# CopernicusBasicTestCircuit.net
KiCad netlist of a schematic drawn in EAGLE
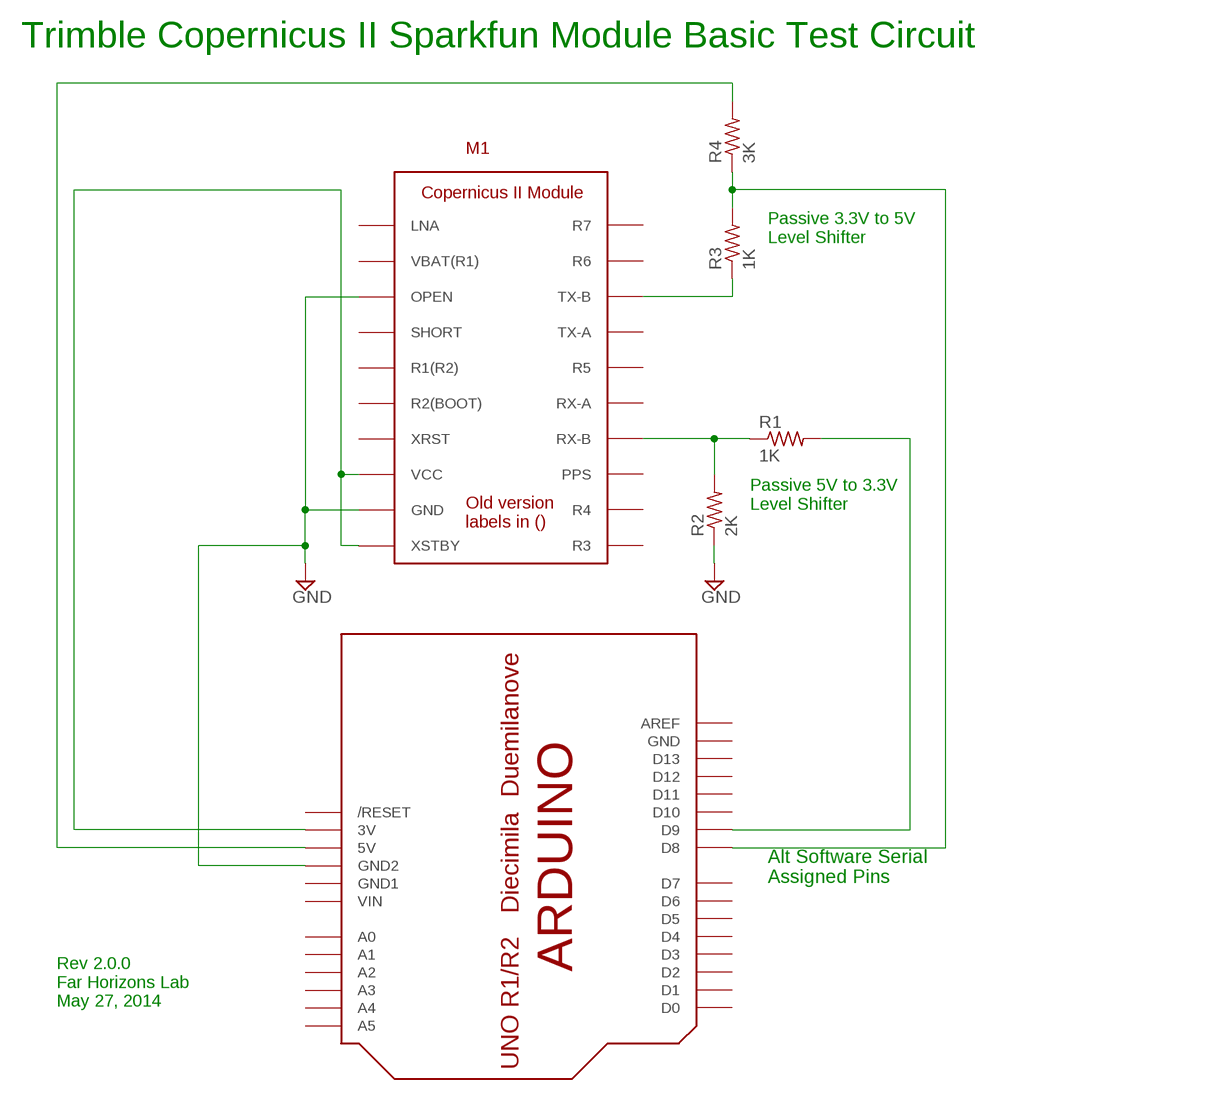
[diagram p0: schematic, sheet 1]

(export (version "E")
  (design (tool "Eeschema 10.0.6"))
  (components
    (comp (ref "M1")
      (value "COPERNICUS_II_MODULE")
      (footprint "eagle-import:COPERNICUS_II_MODULE")
      (libsource (lib "eagle-import") (part "COPERNICUS_II_MODULE"))
    )
    (comp (ref "R1")
      (value "1K")
      (footprint "eagle-import:0207_10")
      (libsource (lib "eagle-import") (part "R-US_0207/10"))
    )
    (comp (ref "R2")
      (value "2K")
      (footprint "eagle-import:0207_10")
      (libsource (lib "eagle-import") (part "R-US_0207/10"))
    )
    (comp (ref "R3")
      (value "1K")
      (footprint "eagle-import:0207_10")
      (libsource (lib "eagle-import") (part "R-US_0207/10"))
    )
    (comp (ref "R4")
      (value "3K")
      (footprint "eagle-import:0207_10")
      (libsource (lib "eagle-import") (part "R-US_0207/10"))
    )
    (comp (ref "U$1")
      (value "ARDUINOUNO")
      (footprint "eagle-import:ARDUINO")
      (libsource (lib "eagle-import") (part "ARDUINOUNO"))
    )
  )
  (nets
    (net (code "1") (name "GND") (class "Default")
      (node (ref "M1") (pin "P$3") (pinfunction "OPEN_P$3") (pintype "bidirectional"))
      (node (ref "M1") (pin "P$9") (pinfunction "GND_P$9") (pintype "bidirectional"))
      (node (ref "R2") (pin "1") (pinfunction "1_1") (pintype "passive"))
      (node (ref "U$1") (pin "GND2") (pinfunction "GND2_GND2") (pintype "bidirectional"))
    )
    (net (code "2") (name "Net-(M1-RX-B)") (class "Default")
      (node (ref "M1") (pin "P$14") (pinfunction "RX-B_P$14") (pintype "bidirectional"))
      (node (ref "R1") (pin "1") (pinfunction "1_1") (pintype "passive"))
      (node (ref "R2") (pin "2") (pinfunction "2_2") (pintype "passive"))
    )
    (net (code "3") (name "Net-(M1-TX-B)") (class "Default")
      (node (ref "M1") (pin "P$18") (pinfunction "TX-B_P$18") (pintype "bidirectional"))
      (node (ref "R3") (pin "1") (pinfunction "1_1") (pintype "passive"))
    )
    (net (code "4") (name "Net-(M1-VCC)") (class "Default")
      (node (ref "M1") (pin "P$10") (pinfunction "XSTBY_P$10") (pintype "bidirectional"))
      (node (ref "M1") (pin "P$8") (pinfunction "VCC_P$8") (pintype "bidirectional"))
      (node (ref "U$1") (pin "3V") (pinfunction "3V_3V") (pintype "output"))
    )
    (net (code "5") (name "Net-(R1-Pad2)") (class "Default")
      (node (ref "R1") (pin "2") (pinfunction "2_2") (pintype "passive"))
      (node (ref "U$1") (pin "D9") (pinfunction "D9_D9") (pintype "bidirectional"))
    )
    (net (code "6") (name "Net-(R3-Pad2)") (class "Default")
      (node (ref "R3") (pin "2") (pinfunction "2_2") (pintype "passive"))
      (node (ref "R4") (pin "1") (pinfunction "1_1") (pintype "passive"))
      (node (ref "U$1") (pin "D8") (pinfunction "D8_D8") (pintype "bidirectional"))
    )
    (net (code "7") (name "Net-(R4-Pad2)") (class "Default")
      (node (ref "R4") (pin "2") (pinfunction "2_2") (pintype "passive"))
      (node (ref "U$1") (pin "5V") (pinfunction "5V_5V") (pintype "output"))
    )
    (net (code "8") (name "unconnected-(M1-LNA-PadP$1)") (class "Default")
      (node (ref "M1") (pin "P$1") (pinfunction "LNA_P$1") (pintype "bidirectional"))
    )
    (net (code "9") (name "unconnected-(M1-PPS-PadP$13)") (class "Default")
      (node (ref "M1") (pin "P$13") (pinfunction "PPS_P$13") (pintype "bidirectional"))
    )
    (net (code "10") (name "unconnected-(M1-R1(R2)-PadP$5)") (class "Default")
      (node (ref "M1") (pin "P$5") (pinfunction "R1(R2)_P$5") (pintype "bidirectional"))
    )
    (net (code "11") (name "unconnected-(M1-R2(BOOT)-PadP$6)") (class "Default")
      (node (ref "M1") (pin "P$6") (pinfunction "R2(BOOT)_P$6") (pintype "bidirectional"))
    )
    (net (code "12") (name "unconnected-(M1-R3-PadP$11)") (class "Default")
      (node (ref "M1") (pin "P$11") (pinfunction "R3_P$11") (pintype "bidirectional"))
    )
    (net (code "13") (name "unconnected-(M1-R4-PadP$12)") (class "Default")
      (node (ref "M1") (pin "P$12") (pinfunction "R4_P$12") (pintype "bidirectional"))
    )
    (net (code "14") (name "unconnected-(M1-R5-PadP$16)") (class "Default")
      (node (ref "M1") (pin "P$16") (pinfunction "R5_P$16") (pintype "bidirectional"))
    )
    (net (code "15") (name "unconnected-(M1-R6-PadP$19)") (class "Default")
      (node (ref "M1") (pin "P$19") (pinfunction "R6_P$19") (pintype "bidirectional"))
    )
    (net (code "16") (name "unconnected-(M1-R7-PadP$20)") (class "Default")
      (node (ref "M1") (pin "P$20") (pinfunction "R7_P$20") (pintype "bidirectional"))
    )
    (net (code "17") (name "unconnected-(M1-RX-A-PadP$15)") (class "Default")
      (node (ref "M1") (pin "P$15") (pinfunction "RX-A_P$15") (pintype "bidirectional"))
    )
    (net (code "18") (name "unconnected-(M1-SHORT-PadP$4)") (class "Default")
      (node (ref "M1") (pin "P$4") (pinfunction "SHORT_P$4") (pintype "bidirectional"))
    )
    (net (code "19") (name "unconnected-(M1-TX-A-PadP$17)") (class "Default")
      (node (ref "M1") (pin "P$17") (pinfunction "TX-A_P$17") (pintype "bidirectional"))
    )
    (net (code "20") (name "unconnected-(M1-VBAT(R1)-PadP$2)") (class "Default")
      (node (ref "M1") (pin "P$2") (pinfunction "VBAT(R1)_P$2") (pintype "bidirectional"))
    )
    (net (code "21") (name "unconnected-(M1-XRST-PadP$7)") (class "Default")
      (node (ref "M1") (pin "P$7") (pinfunction "XRST_P$7") (pintype "bidirectional"))
    )
    (net (code "22") (name "unconnected-(U$1-PadA0)") (class "Default")
      (node (ref "U$1") (pin "A0") (pinfunction "A0_A0") (pintype "bidirectional"))
    )
    (net (code "23") (name "unconnected-(U$1-PadA1)") (class "Default")
      (node (ref "U$1") (pin "A1") (pinfunction "A1_A1") (pintype "bidirectional"))
    )
    (net (code "24") (name "unconnected-(U$1-PadA2)") (class "Default")
      (node (ref "U$1") (pin "A2") (pinfunction "A2_A2") (pintype "bidirectional"))
    )
    (net (code "25") (name "unconnected-(U$1-PadA3)") (class "Default")
      (node (ref "U$1") (pin "A3") (pinfunction "A3_A3") (pintype "bidirectional"))
    )
    (net (code "26") (name "unconnected-(U$1-PadA4)") (class "Default")
      (node (ref "U$1") (pin "A4") (pinfunction "A4_A4") (pintype "bidirectional"))
    )
    (net (code "27") (name "unconnected-(U$1-PadA5)") (class "Default")
      (node (ref "U$1") (pin "A5") (pinfunction "A5_A5") (pintype "bidirectional"))
    )
    (net (code "28") (name "unconnected-(U$1-PadAREF)") (class "Default")
      (node (ref "U$1") (pin "AREF") (pinfunction "AREF_AREF") (pintype "bidirectional"))
    )
    (net (code "29") (name "unconnected-(U$1-PadD0)") (class "Default")
      (node (ref "U$1") (pin "D0") (pinfunction "D0_D0") (pintype "bidirectional"))
    )
    (net (code "30") (name "unconnected-(U$1-PadD1)") (class "Default")
      (node (ref "U$1") (pin "D1") (pinfunction "D1_D1") (pintype "bidirectional"))
    )
    (net (code "31") (name "unconnected-(U$1-PadD2)") (class "Default")
      (node (ref "U$1") (pin "D2") (pinfunction "D2_D2") (pintype "bidirectional"))
    )
    (net (code "32") (name "unconnected-(U$1-PadD3)") (class "Default")
      (node (ref "U$1") (pin "D3") (pinfunction "D3_D3") (pintype "bidirectional"))
    )
    (net (code "33") (name "unconnected-(U$1-PadD4)") (class "Default")
      (node (ref "U$1") (pin "D4") (pinfunction "D4_D4") (pintype "bidirectional"))
    )
    (net (code "34") (name "unconnected-(U$1-PadD5)") (class "Default")
      (node (ref "U$1") (pin "D5") (pinfunction "D5_D5") (pintype "bidirectional"))
    )
    (net (code "35") (name "unconnected-(U$1-PadD6)") (class "Default")
      (node (ref "U$1") (pin "D6") (pinfunction "D6_D6") (pintype "bidirectional"))
    )
    (net (code "36") (name "unconnected-(U$1-PadD7)") (class "Default")
      (node (ref "U$1") (pin "D7") (pinfunction "D7_D7") (pintype "bidirectional"))
    )
    (net (code "37") (name "unconnected-(U$1-PadD10)") (class "Default")
      (node (ref "U$1") (pin "D10") (pinfunction "D10_D10") (pintype "bidirectional"))
    )
    (net (code "38") (name "unconnected-(U$1-PadD11)") (class "Default")
      (node (ref "U$1") (pin "D11") (pinfunction "D11_D11") (pintype "bidirectional"))
    )
    (net (code "39") (name "unconnected-(U$1-PadD12)") (class "Default")
      (node (ref "U$1") (pin "D12") (pinfunction "D12_D12") (pintype "bidirectional"))
    )
    (net (code "40") (name "unconnected-(U$1-PadD13)") (class "Default")
      (node (ref "U$1") (pin "D13") (pinfunction "D13_D13") (pintype "bidirectional"))
    )
    (net (code "41") (name "unconnected-(U$1-PadGND)") (class "Default")
      (node (ref "U$1") (pin "GND") (pinfunction "GND_GND") (pintype "bidirectional"))
    )
    (net (code "42") (name "unconnected-(U$1-PadGND1)") (class "Default")
      (node (ref "U$1") (pin "GND1") (pinfunction "GND1_GND1") (pintype "bidirectional"))
    )
    (net (code "43") (name "unconnected-(U$1-PadVIN)") (class "Default")
      (node (ref "U$1") (pin "VIN") (pinfunction "VIN_VIN") (pintype "bidirectional"))
    )
    (net (code "44") (name "unconnected-(U$1-{slash}RESET-PadRESET)") (class "Default")
      (node (ref "U$1") (pin "RESET") (pinfunction "/RESET_RESET") (pintype "bidirectional"))
    )
  )
)
